# kuro_side.net
KiCad netlist of a schematic drawn in EAGLE
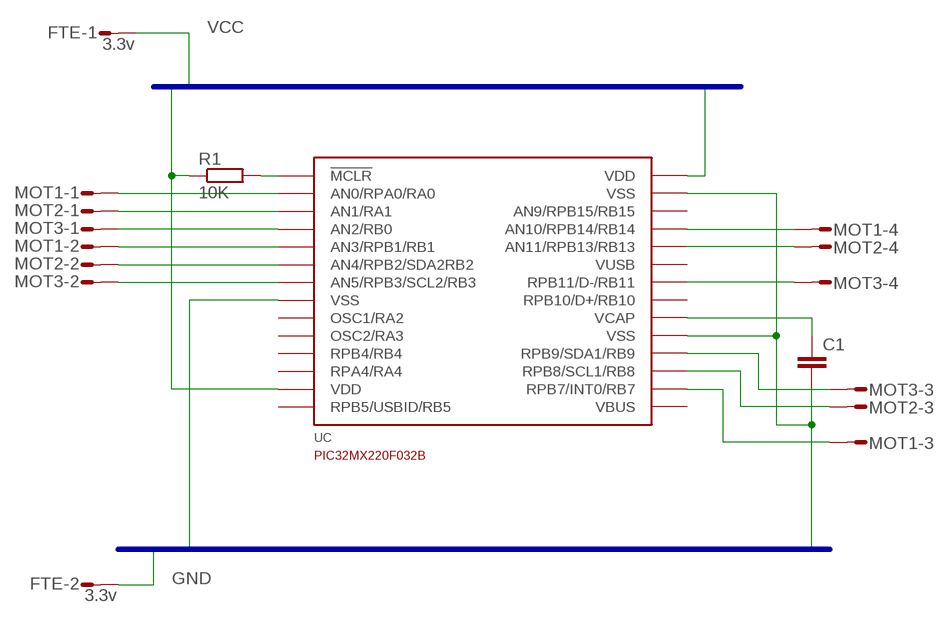
[diagram p0: schematic, sheet 1]

(export (version "E")
  (design (tool "Eeschema 10.0.6"))
  (components
    (comp (ref "C1")
      (value "C2,5-3")
      (footprint "eagle-import:C2.5-3")
      (libsource (lib "eagle-import") (part "C2,5-3"))
    )
    (comp (ref "FTE")
      (value "3.3v")
      (footprint "eagle-import:S02P")
      (libsource (lib "eagle-import") (part "S02P"))
    )
    (comp (ref "MOT1")
      (value "S04P")
      (footprint "eagle-import:S04P")
      (libsource (lib "eagle-import") (part "S04P"))
    )
    (comp (ref "MOT2")
      (value "S04P")
      (footprint "eagle-import:S04P")
      (libsource (lib "eagle-import") (part "S04P"))
    )
    (comp (ref "MOT3")
      (value "S04P")
      (footprint "eagle-import:S04P")
      (libsource (lib "eagle-import") (part "S04P"))
    )
    (comp (ref "R1")
      (value "10K")
      (footprint "eagle-import:0207_10")
      (libsource (lib "eagle-import") (part "R-EU_0207/10"))
    )
    (comp (ref "UC")
      (value "PIC32MX220F032B")
      (footprint "eagle-import:DIP28")
      (libsource (lib "eagle-import") (part "PIC32MX220F032B"))
    )
  )
  (nets
    (net (code "1") (name "/GND") (class "Default")
      (node (ref "C1") (pin "2") (pinfunction "2_2") (pintype "passive"))
      (node (ref "FTE") (pin "2") (pinfunction "S_2") (pintype "passive"))
      (node (ref "UC") (pin "P$19") (pinfunction "VSS_P$19") (pintype "power_in"))
      (node (ref "UC") (pin "P$27") (pinfunction "VSS_P$27") (pintype "power_in"))
      (node (ref "UC") (pin "P$8") (pinfunction "VSS_P$8") (pintype "power_in"))
    )
    (net (code "2") (name "/VCC") (class "Default")
      (node (ref "FTE") (pin "1") (pinfunction "S_1") (pintype "passive"))
      (node (ref "R1") (pin "1") (pinfunction "1_1") (pintype "passive"))
      (node (ref "UC") (pin "P$13") (pinfunction "VDD_P$13") (pintype "power_in"))
      (node (ref "UC") (pin "P$28") (pinfunction "VDD_P$28") (pintype "power_in"))
    )
    (net (code "3") (name "/VUSB") (class "Default")
      (node (ref "UC") (pin "P$15") (pinfunction "VUSB_P$15") (pintype "power_in"))
    )
    (net (code "4") (name "Net-(MOT1A-S)") (class "Default")
      (node (ref "MOT1") (pin "1") (pinfunction "S_1") (pintype "passive"))
      (node (ref "UC") (pin "P$2") (pinfunction "AN0/RPA0/RA0_P$2") (pintype "bidirectional"))
    )
    (net (code "5") (name "Net-(MOT1B-S)") (class "Default")
      (node (ref "MOT1") (pin "2") (pinfunction "S_2") (pintype "passive"))
      (node (ref "UC") (pin "P$5") (pinfunction "AN3/RPB1/RB1_P$5") (pintype "bidirectional"))
    )
    (net (code "6") (name "Net-(MOT1C-S)") (class "Default")
      (node (ref "MOT1") (pin "3") (pinfunction "S_3") (pintype "passive"))
      (node (ref "UC") (pin "P$16") (pinfunction "RPB7/INT0/RB7_P$16") (pintype "bidirectional"))
    )
    (net (code "7") (name "Net-(MOT1D-S)") (class "Default")
      (node (ref "MOT1") (pin "4") (pinfunction "S_4") (pintype "passive"))
      (node (ref "UC") (pin "P$25") (pinfunction "AN10/RPB14/RB14_P$25") (pintype "bidirectional"))
    )
    (net (code "8") (name "Net-(MOT2A-S)") (class "Default")
      (node (ref "MOT2") (pin "1") (pinfunction "S_1") (pintype "passive"))
      (node (ref "UC") (pin "P$3") (pinfunction "AN1/RA1_P$3") (pintype "bidirectional"))
    )
    (net (code "9") (name "Net-(MOT2B-S)") (class "Default")
      (node (ref "MOT2") (pin "2") (pinfunction "S_2") (pintype "passive"))
      (node (ref "UC") (pin "P$6") (pinfunction "AN4/RPB2/SDA2RB2_P$6") (pintype "bidirectional"))
    )
    (net (code "10") (name "Net-(MOT2C-S)") (class "Default")
      (node (ref "MOT2") (pin "3") (pinfunction "S_3") (pintype "passive"))
      (node (ref "UC") (pin "P$17") (pinfunction "RPB8/SCL1/RB8_P$17") (pintype "bidirectional"))
    )
    (net (code "11") (name "Net-(MOT2D-S)") (class "Default")
      (node (ref "MOT2") (pin "4") (pinfunction "S_4") (pintype "passive"))
      (node (ref "UC") (pin "P$24") (pinfunction "AN11/RPB13/RB13_P$24") (pintype "bidirectional"))
    )
    (net (code "12") (name "Net-(MOT3A-S)") (class "Default")
      (node (ref "MOT3") (pin "1") (pinfunction "S_1") (pintype "passive"))
      (node (ref "UC") (pin "P$4") (pinfunction "AN2/RB0_P$4") (pintype "bidirectional"))
    )
    (net (code "13") (name "Net-(MOT3B-S)") (class "Default")
      (node (ref "MOT3") (pin "2") (pinfunction "S_2") (pintype "passive"))
      (node (ref "UC") (pin "P$7") (pinfunction "AN5/RPB3/SCL2/RB3_P$7") (pintype "bidirectional"))
    )
    (net (code "14") (name "Net-(MOT3C-S)") (class "Default")
      (node (ref "MOT3") (pin "3") (pinfunction "S_3") (pintype "passive"))
      (node (ref "UC") (pin "P$18") (pinfunction "RPB9/SDA1/RB9_P$18") (pintype "bidirectional"))
    )
    (net (code "15") (name "Net-(MOT3D-S)") (class "Default")
      (node (ref "MOT3") (pin "4") (pinfunction "S_4") (pintype "passive"))
      (node (ref "UC") (pin "P$22") (pinfunction "RPB11/D-/RB11_P$22") (pintype "bidirectional"))
    )
    (net (code "16") (name "Net-(UC-VCAP)") (class "Default")
      (node (ref "C1") (pin "1") (pinfunction "1_1") (pintype "passive"))
      (node (ref "UC") (pin "P$20") (pinfunction "VCAP_P$20") (pintype "bidirectional"))
    )
    (net (code "17") (name "Net-(UC-~{MCLR})") (class "Default")
      (node (ref "R1") (pin "2") (pinfunction "2_2") (pintype "passive"))
      (node (ref "UC") (pin "P$1") (pinfunction "~{MCLR}_P$1") (pintype "bidirectional"))
    )
    (net (code "18") (name "unconnected-(UC-AN9{slash}RPB15{slash}RB15-PadP$26)") (class "Default")
      (node (ref "UC") (pin "P$26") (pinfunction "AN9/RPB15/RB15_P$26") (pintype "bidirectional"))
    )
    (net (code "19") (name "unconnected-(UC-OSC1{slash}RA2-PadP$9)") (class "Default")
      (node (ref "UC") (pin "P$9") (pinfunction "OSC1/RA2_P$9") (pintype "bidirectional"))
    )
    (net (code "20") (name "unconnected-(UC-OSC2{slash}RA3-PadP$10)") (class "Default")
      (node (ref "UC") (pin "P$10") (pinfunction "OSC2/RA3_P$10") (pintype "bidirectional"))
    )
    (net (code "21") (name "unconnected-(UC-RPA4{slash}RA4-PadP$12)") (class "Default")
      (node (ref "UC") (pin "P$12") (pinfunction "RPA4/RA4_P$12") (pintype "bidirectional"))
    )
    (net (code "22") (name "unconnected-(UC-RPB4{slash}RB4-PadP$11)") (class "Default")
      (node (ref "UC") (pin "P$11") (pinfunction "RPB4/RB4_P$11") (pintype "bidirectional"))
    )
    (net (code "23") (name "unconnected-(UC-RPB5{slash}USBID{slash}RB5-PadP$14)") (class "Default")
      (node (ref "UC") (pin "P$14") (pinfunction "RPB5/USBID/RB5_P$14") (pintype "bidirectional"))
    )
    (net (code "24") (name "unconnected-(UC-RPB10{slash}D+{slash}RB10-PadP$21)") (class "Default")
      (node (ref "UC") (pin "P$21") (pinfunction "RPB10/D+/RB10_P$21") (pintype "bidirectional"))
    )
    (net (code "25") (name "unconnected-(UC-VBUS-PadP$23)") (class "Default")
      (node (ref "UC") (pin "P$23") (pinfunction "VBUS_P$23") (pintype "bidirectional"))
    )
  )
)
